# Teensy-Long.net
KiCad netlist of a schematic drawn in EAGLE
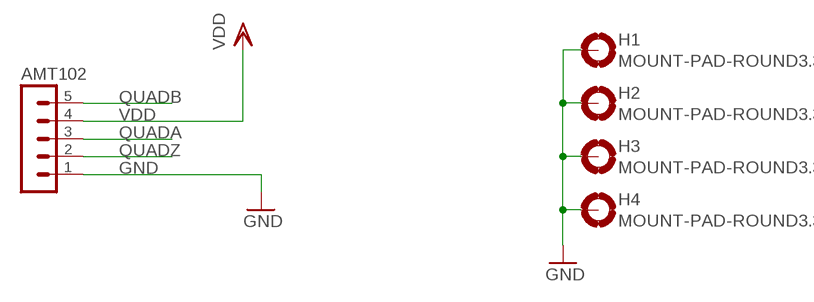
[diagram p0: schematic, sheet 1]
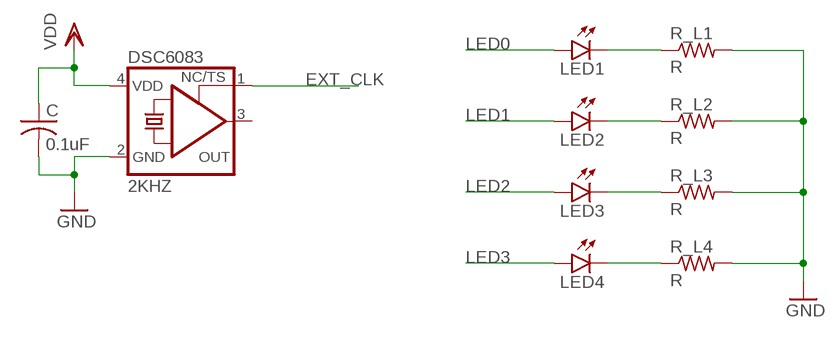
[diagram p1: schematic, sheet 2]
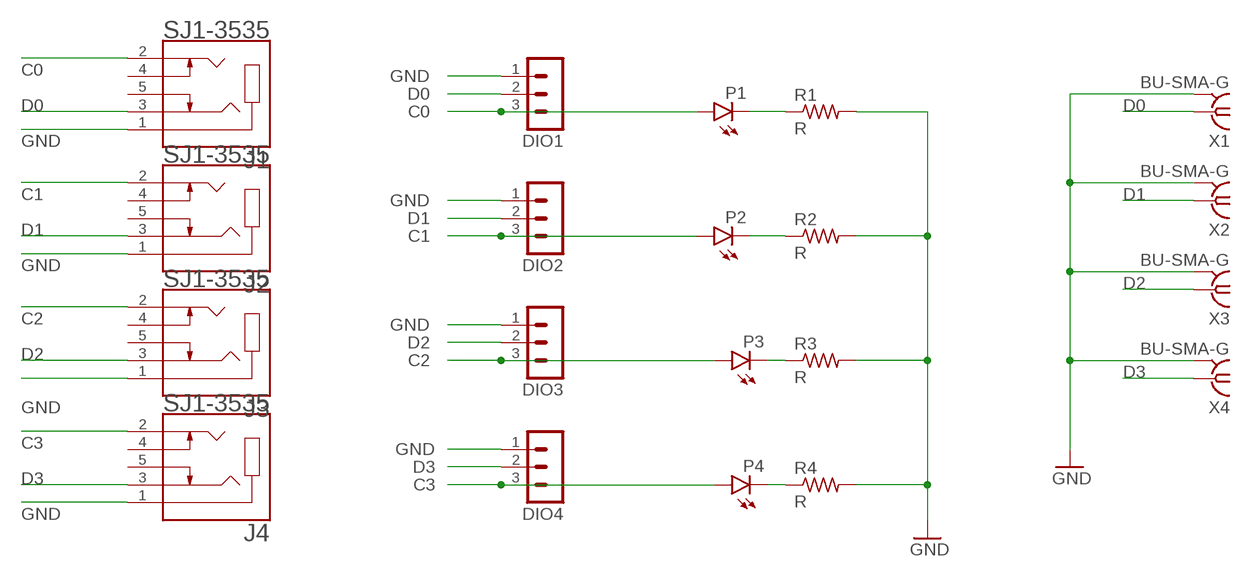
[diagram p2: schematic, sheet 3]
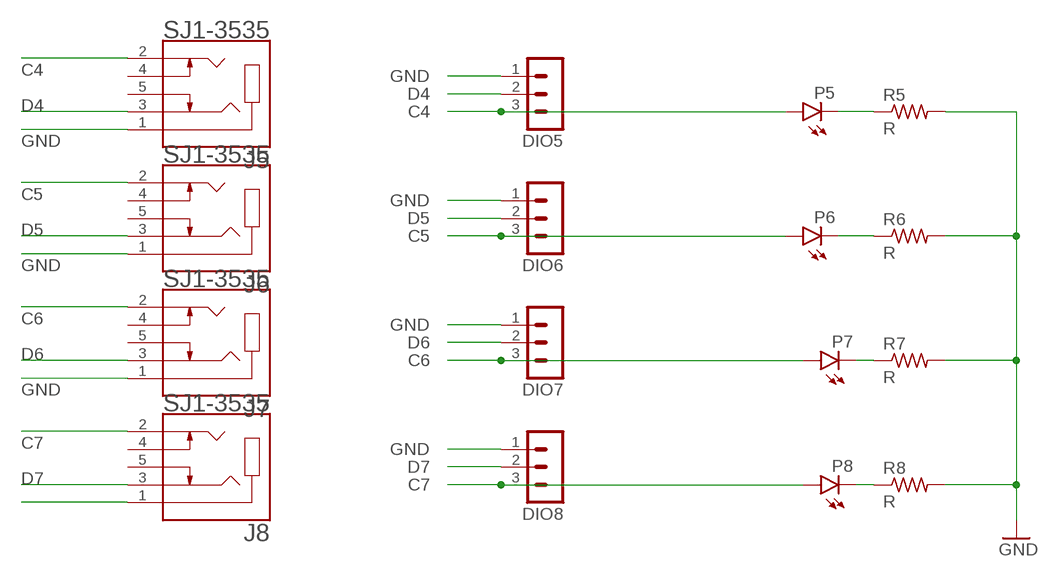
[diagram p3: schematic, sheet 4]
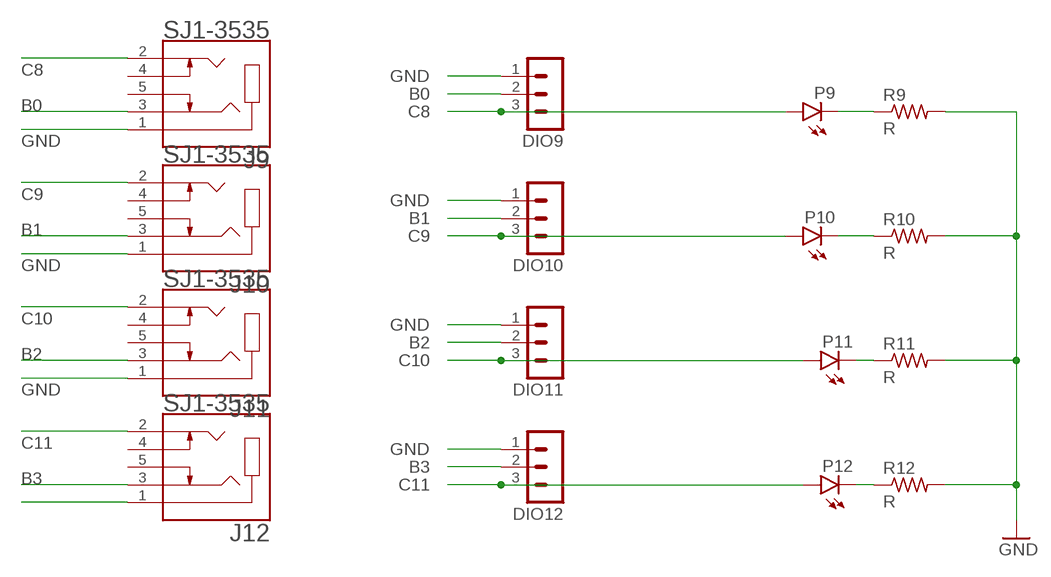
[diagram p4: schematic, sheet 5]
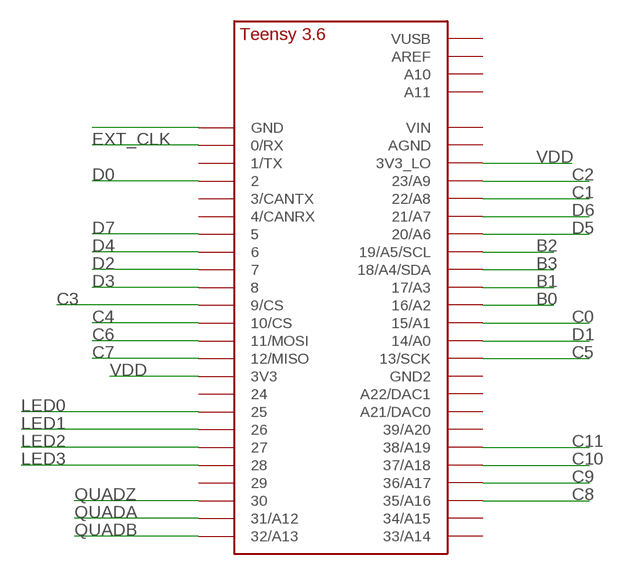
[diagram p5: schematic, sheet 6]

(export (version "E")
  (design (tool "Eeschema 10.0.6"))
  (components
    (comp (ref "C")
      (value "0.1uF")
      (footprint "eagle-import:C0603")
      (libsource (lib "eagle-import") (part "C-USC0603"))
    )
    (comp (ref "DSC6083")
      (value "2KHZ")
      (footprint "eagle-import:3.2X2.5_KXO-V96")
      (libsource (lib "eagle-import") (part "KXO-PXO/XO-V96"))
    )
    (comp (ref "LED1")
      (value "LEDCHIP-LED0603")
      (footprint "eagle-import:CHIP-LED0603")
      (libsource (lib "eagle-import") (part "LEDCHIP-LED0603"))
    )
    (comp (ref "LED2")
      (value "LEDCHIP-LED0603")
      (footprint "eagle-import:CHIP-LED0603")
      (libsource (lib "eagle-import") (part "LEDCHIP-LED0603"))
    )
    (comp (ref "LED3")
      (value "LEDCHIP-LED0603")
      (footprint "eagle-import:CHIP-LED0603")
      (libsource (lib "eagle-import") (part "LEDCHIP-LED0603"))
    )
    (comp (ref "LED4")
      (value "LEDCHIP-LED0603")
      (footprint "eagle-import:CHIP-LED0603")
      (libsource (lib "eagle-import") (part "LEDCHIP-LED0603"))
    )
    (comp (ref "R_L1")
      (value "R")
      (footprint "eagle-import:R0603")
      (libsource (lib "eagle-import") (part "R-US_R0603"))
    )
    (comp (ref "R_L2")
      (value "R")
      (footprint "eagle-import:R0603")
      (libsource (lib "eagle-import") (part "R-US_R0603"))
    )
    (comp (ref "R_L3")
      (value "R")
      (footprint "eagle-import:R0603")
      (libsource (lib "eagle-import") (part "R-US_R0603"))
    )
    (comp (ref "R_L4")
      (value "R")
      (footprint "eagle-import:R0603")
      (libsource (lib "eagle-import") (part "R-US_R0603"))
    )
    (comp (ref "U$3")
      (value "TEENSY_3.5/3.6_BASIC")
      (footprint "eagle-import:TEENSY_3.5_3.6_BASIC")
      (libsource (lib "eagle-import") (part "TEENSY_3.5/3.6_BASIC"))
    )
    (comp (ref "DIO9")
      (value "MA03-1")
      (footprint "eagle-import:MA03-1")
      (libsource (lib "eagle-import") (part "MA03-1"))
    )
    (comp (ref "DIO10")
      (value "MA03-1")
      (footprint "eagle-import:MA03-1")
      (libsource (lib "eagle-import") (part "MA03-1"))
    )
    (comp (ref "DIO11")
      (value "MA03-1")
      (footprint "eagle-import:MA03-1")
      (libsource (lib "eagle-import") (part "MA03-1"))
    )
    (comp (ref "DIO12")
      (value "MA03-1")
      (footprint "eagle-import:MA03-1")
      (libsource (lib "eagle-import") (part "MA03-1"))
    )
    (comp (ref "J9")
      (value "SJ1-3535")
      (footprint "eagle-import:CUI_SJ1-3535")
      (fields (field (name "MF") "CUI Devices"))
      (libsource (lib "eagle-import") (part "SJ1-3535"))
    )
    (comp (ref "J10")
      (value "SJ1-3535")
      (footprint "eagle-import:CUI_SJ1-3535")
      (fields (field (name "MF") "CUI Devices"))
      (libsource (lib "eagle-import") (part "SJ1-3535"))
    )
    (comp (ref "J11")
      (value "SJ1-3535")
      (footprint "eagle-import:CUI_SJ1-3535")
      (fields (field (name "MF") "CUI Devices"))
      (libsource (lib "eagle-import") (part "SJ1-3535"))
    )
    (comp (ref "J12")
      (value "SJ1-3535")
      (footprint "eagle-import:CUI_SJ1-3535")
      (fields (field (name "MF") "CUI Devices"))
      (libsource (lib "eagle-import") (part "SJ1-3535"))
    )
    (comp (ref "P9")
      (value "LEDCHIP-LED0603")
      (footprint "eagle-import:CHIP-LED0603")
      (libsource (lib "eagle-import") (part "LEDCHIP-LED0603"))
    )
    (comp (ref "P10")
      (value "LEDCHIP-LED0603")
      (footprint "eagle-import:CHIP-LED0603")
      (libsource (lib "eagle-import") (part "LEDCHIP-LED0603"))
    )
    (comp (ref "P11")
      (value "LEDCHIP-LED0603")
      (footprint "eagle-import:CHIP-LED0603")
      (libsource (lib "eagle-import") (part "LEDCHIP-LED0603"))
    )
    (comp (ref "P12")
      (value "LEDCHIP-LED0603")
      (footprint "eagle-import:CHIP-LED0603")
      (libsource (lib "eagle-import") (part "LEDCHIP-LED0603"))
    )
    (comp (ref "R9")
      (value "R")
      (footprint "eagle-import:R0603")
      (libsource (lib "eagle-import") (part "R-US_R0603"))
    )
    (comp (ref "R10")
      (value "R")
      (footprint "eagle-import:R0603")
      (libsource (lib "eagle-import") (part "R-US_R0603"))
    )
    (comp (ref "R11")
      (value "R")
      (footprint "eagle-import:R0603")
      (libsource (lib "eagle-import") (part "R-US_R0603"))
    )
    (comp (ref "R12")
      (value "R")
      (footprint "eagle-import:R0603")
      (libsource (lib "eagle-import") (part "R-US_R0603"))
    )
    (comp (ref "DIO5")
      (value "MA03-1")
      (footprint "eagle-import:MA03-1")
      (libsource (lib "eagle-import") (part "MA03-1"))
    )
    (comp (ref "DIO6")
      (value "MA03-1")
      (footprint "eagle-import:MA03-1")
      (libsource (lib "eagle-import") (part "MA03-1"))
    )
    (comp (ref "DIO7")
      (value "MA03-1")
      (footprint "eagle-import:MA03-1")
      (libsource (lib "eagle-import") (part "MA03-1"))
    )
    (comp (ref "DIO8")
      (value "MA03-1")
      (footprint "eagle-import:MA03-1")
      (libsource (lib "eagle-import") (part "MA03-1"))
    )
    (comp (ref "J5")
      (value "SJ1-3535")
      (footprint "eagle-import:CUI_SJ1-3535")
      (fields (field (name "MF") "CUI Devices"))
      (libsource (lib "eagle-import") (part "SJ1-3535"))
    )
    (comp (ref "J6")
      (value "SJ1-3535")
      (footprint "eagle-import:CUI_SJ1-3535")
      (fields (field (name "MF") "CUI Devices"))
      (libsource (lib "eagle-import") (part "SJ1-3535"))
    )
    (comp (ref "J7")
      (value "SJ1-3535")
      (footprint "eagle-import:CUI_SJ1-3535")
      (fields (field (name "MF") "CUI Devices"))
      (libsource (lib "eagle-import") (part "SJ1-3535"))
    )
    (comp (ref "J8")
      (value "SJ1-3535")
      (footprint "eagle-import:CUI_SJ1-3535")
      (fields (field (name "MF") "CUI Devices"))
      (libsource (lib "eagle-import") (part "SJ1-3535"))
    )
    (comp (ref "P5")
      (value "LEDCHIP-LED0603")
      (footprint "eagle-import:CHIP-LED0603")
      (libsource (lib "eagle-import") (part "LEDCHIP-LED0603"))
    )
    (comp (ref "P6")
      (value "LEDCHIP-LED0603")
      (footprint "eagle-import:CHIP-LED0603")
      (libsource (lib "eagle-import") (part "LEDCHIP-LED0603"))
    )
    (comp (ref "P7")
      (value "LEDCHIP-LED0603")
      (footprint "eagle-import:CHIP-LED0603")
      (libsource (lib "eagle-import") (part "LEDCHIP-LED0603"))
    )
    (comp (ref "P8")
      (value "LEDCHIP-LED0603")
      (footprint "eagle-import:CHIP-LED0603")
      (libsource (lib "eagle-import") (part "LEDCHIP-LED0603"))
    )
    (comp (ref "R5")
      (value "R")
      (footprint "eagle-import:R0603")
      (libsource (lib "eagle-import") (part "R-US_R0603"))
    )
    (comp (ref "R6")
      (value "R")
      (footprint "eagle-import:R0603")
      (libsource (lib "eagle-import") (part "R-US_R0603"))
    )
    (comp (ref "R7")
      (value "R")
      (footprint "eagle-import:R0603")
      (libsource (lib "eagle-import") (part "R-US_R0603"))
    )
    (comp (ref "R8")
      (value "R")
      (footprint "eagle-import:R0603")
      (libsource (lib "eagle-import") (part "R-US_R0603"))
    )
    (comp (ref "AMT102")
      (value "MA05-1")
      (footprint "eagle-import:MA05-1")
      (libsource (lib "eagle-import") (part "MA05-1"))
    )
    (comp (ref "H1")
      (value "MOUNT-PAD-ROUND3.3")
      (footprint "eagle-import:3,3-PAD")
      (libsource (lib "eagle-import") (part "MOUNT-PAD-ROUND3.3"))
    )
    (comp (ref "H2")
      (value "MOUNT-PAD-ROUND3.3")
      (footprint "eagle-import:3,3-PAD")
      (libsource (lib "eagle-import") (part "MOUNT-PAD-ROUND3.3"))
    )
    (comp (ref "H3")
      (value "MOUNT-PAD-ROUND3.3")
      (footprint "eagle-import:3,3-PAD")
      (libsource (lib "eagle-import") (part "MOUNT-PAD-ROUND3.3"))
    )
    (comp (ref "H4")
      (value "MOUNT-PAD-ROUND3.3")
      (footprint "eagle-import:3,3-PAD")
      (libsource (lib "eagle-import") (part "MOUNT-PAD-ROUND3.3"))
    )
    (comp (ref "DIO1")
      (value "MA03-1")
      (footprint "eagle-import:MA03-1")
      (libsource (lib "eagle-import") (part "MA03-1"))
    )
    (comp (ref "DIO2")
      (value "MA03-1")
      (footprint "eagle-import:MA03-1")
      (libsource (lib "eagle-import") (part "MA03-1"))
    )
    (comp (ref "DIO3")
      (value "MA03-1")
      (footprint "eagle-import:MA03-1")
      (libsource (lib "eagle-import") (part "MA03-1"))
    )
    (comp (ref "DIO4")
      (value "MA03-1")
      (footprint "eagle-import:MA03-1")
      (libsource (lib "eagle-import") (part "MA03-1"))
    )
    (comp (ref "J1")
      (value "SJ1-3535")
      (footprint "eagle-import:CUI_SJ1-3535")
      (fields (field (name "MF") "CUI Devices"))
      (libsource (lib "eagle-import") (part "SJ1-3535"))
    )
    (comp (ref "J2")
      (value "SJ1-3535")
      (footprint "eagle-import:CUI_SJ1-3535")
      (fields (field (name "MF") "CUI Devices"))
      (libsource (lib "eagle-import") (part "SJ1-3535"))
    )
    (comp (ref "J3")
      (value "SJ1-3535")
      (footprint "eagle-import:CUI_SJ1-3535")
      (fields (field (name "MF") "CUI Devices"))
      (libsource (lib "eagle-import") (part "SJ1-3535"))
    )
    (comp (ref "J4")
      (value "SJ1-3535")
      (footprint "eagle-import:CUI_SJ1-3535")
      (fields (field (name "MF") "CUI Devices"))
      (libsource (lib "eagle-import") (part "SJ1-3535"))
    )
    (comp (ref "P1")
      (value "LEDCHIP-LED0603")
      (footprint "eagle-import:CHIP-LED0603")
      (libsource (lib "eagle-import") (part "LEDCHIP-LED0603"))
    )
    (comp (ref "P2")
      (value "LEDCHIP-LED0603")
      (footprint "eagle-import:CHIP-LED0603")
      (libsource (lib "eagle-import") (part "LEDCHIP-LED0603"))
    )
    (comp (ref "P3")
      (value "LEDCHIP-LED0603")
      (footprint "eagle-import:CHIP-LED0603")
      (libsource (lib "eagle-import") (part "LEDCHIP-LED0603"))
    )
    (comp (ref "P4")
      (value "LEDCHIP-LED0603")
      (footprint "eagle-import:CHIP-LED0603")
      (libsource (lib "eagle-import") (part "LEDCHIP-LED0603"))
    )
    (comp (ref "R1")
      (value "R")
      (footprint "eagle-import:R0603")
      (libsource (lib "eagle-import") (part "R-US_R0603"))
    )
    (comp (ref "R2")
      (value "R")
      (footprint "eagle-import:R0603")
      (libsource (lib "eagle-import") (part "R-US_R0603"))
    )
    (comp (ref "R3")
      (value "R")
      (footprint "eagle-import:R0603")
      (libsource (lib "eagle-import") (part "R-US_R0603"))
    )
    (comp (ref "R4")
      (value "R")
      (footprint "eagle-import:R0603")
      (libsource (lib "eagle-import") (part "R-US_R0603"))
    )
    (comp (ref "X1")
      (value "BU-SMA-G")
      (footprint "eagle-import:BU-SMA-G")
      (libsource (lib "eagle-import") (part "BU-SMA-G"))
    )
    (comp (ref "X2")
      (value "BU-SMA-G")
      (footprint "eagle-import:BU-SMA-G")
      (libsource (lib "eagle-import") (part "BU-SMA-G"))
    )
    (comp (ref "X3")
      (value "BU-SMA-G")
      (footprint "eagle-import:BU-SMA-G")
      (libsource (lib "eagle-import") (part "BU-SMA-G"))
    )
    (comp (ref "X4")
      (value "BU-SMA-G")
      (footprint "eagle-import:BU-SMA-G")
      (libsource (lib "eagle-import") (part "BU-SMA-G"))
    )
  )
  (nets
    (net (code "1") (name "B0") (class "Default")
      (node (ref "DIO9") (pin "2") (pinfunction "2_2") (pintype "passive"))
      (node (ref "J9") (pin "3") (pinfunction "3_3") (pintype "passive"))
      (node (ref "U$3") (pin "16/A2") (pinfunction "16/A2_16/A2") (pintype "bidirectional"))
    )
    (net (code "2") (name "B1") (class "Default")
      (node (ref "DIO10") (pin "2") (pinfunction "2_2") (pintype "passive"))
      (node (ref "J10") (pin "3") (pinfunction "3_3") (pintype "passive"))
      (node (ref "U$3") (pin "17/A3") (pinfunction "17/A3_17/A3") (pintype "bidirectional"))
    )
    (net (code "3") (name "B2") (class "Default")
      (node (ref "DIO11") (pin "2") (pinfunction "2_2") (pintype "passive"))
      (node (ref "J11") (pin "3") (pinfunction "3_3") (pintype "passive"))
      (node (ref "U$3") (pin "19/A5/SCL") (pinfunction "19/A5/SCL_19/A5/SCL") (pintype "bidirectional"))
    )
    (net (code "4") (name "B3") (class "Default")
      (node (ref "DIO12") (pin "2") (pinfunction "2_2") (pintype "passive"))
      (node (ref "J12") (pin "3") (pinfunction "3_3") (pintype "passive"))
      (node (ref "U$3") (pin "18/A4/SDA") (pinfunction "18/A4/SDA_18/A4/SDA") (pintype "bidirectional"))
    )
    (net (code "5") (name "C0") (class "Default")
      (node (ref "DIO1") (pin "3") (pinfunction "3_3") (pintype "passive"))
      (node (ref "J1") (pin "2") (pinfunction "2_2") (pintype "passive"))
      (node (ref "P1") (pin "A") (pinfunction "A_A") (pintype "passive"))
      (node (ref "U$3") (pin "15/A1") (pinfunction "15/A1_15/A1") (pintype "bidirectional"))
    )
    (net (code "6") (name "C1") (class "Default")
      (node (ref "DIO2") (pin "3") (pinfunction "3_3") (pintype "passive"))
      (node (ref "J2") (pin "2") (pinfunction "2_2") (pintype "passive"))
      (node (ref "P2") (pin "A") (pinfunction "A_A") (pintype "passive"))
      (node (ref "U$3") (pin "22/A8") (pinfunction "22/A8_22/A8") (pintype "bidirectional"))
    )
    (net (code "7") (name "C2") (class "Default")
      (node (ref "DIO3") (pin "3") (pinfunction "3_3") (pintype "passive"))
      (node (ref "J3") (pin "2") (pinfunction "2_2") (pintype "passive"))
      (node (ref "P3") (pin "A") (pinfunction "A_A") (pintype "passive"))
      (node (ref "U$3") (pin "23/A9") (pinfunction "23/A9_23/A9") (pintype "bidirectional"))
    )
    (net (code "8") (name "C3") (class "Default")
      (node (ref "DIO4") (pin "3") (pinfunction "3_3") (pintype "passive"))
      (node (ref "J4") (pin "2") (pinfunction "2_2") (pintype "passive"))
      (node (ref "P4") (pin "A") (pinfunction "A_A") (pintype "passive"))
      (node (ref "U$3") (pin "9/CS") (pinfunction "9/CS_9/CS") (pintype "bidirectional"))
    )
    (net (code "9") (name "C4") (class "Default")
      (node (ref "DIO5") (pin "3") (pinfunction "3_3") (pintype "passive"))
      (node (ref "J5") (pin "2") (pinfunction "2_2") (pintype "passive"))
      (node (ref "P5") (pin "A") (pinfunction "A_A") (pintype "passive"))
      (node (ref "U$3") (pin "10/CS") (pinfunction "10/CS_10/CS") (pintype "bidirectional"))
    )
    (net (code "10") (name "C5") (class "Default")
      (node (ref "DIO6") (pin "3") (pinfunction "3_3") (pintype "passive"))
      (node (ref "J6") (pin "2") (pinfunction "2_2") (pintype "passive"))
      (node (ref "P6") (pin "A") (pinfunction "A_A") (pintype "passive"))
      (node (ref "U$3") (pin "13/SCK") (pinfunction "13/SCK_13/SCK") (pintype "bidirectional"))
    )
    (net (code "11") (name "C6") (class "Default")
      (node (ref "DIO7") (pin "3") (pinfunction "3_3") (pintype "passive"))
      (node (ref "J7") (pin "2") (pinfunction "2_2") (pintype "passive"))
      (node (ref "P7") (pin "A") (pinfunction "A_A") (pintype "passive"))
      (node (ref "U$3") (pin "11/MOSI") (pinfunction "11/MOSI_11/MOSI") (pintype "bidirectional"))
    )
    (net (code "12") (name "C7") (class "Default")
      (node (ref "DIO8") (pin "3") (pinfunction "3_3") (pintype "passive"))
      (node (ref "J8") (pin "2") (pinfunction "2_2") (pintype "passive"))
      (node (ref "P8") (pin "A") (pinfunction "A_A") (pintype "passive"))
      (node (ref "U$3") (pin "12/MISO") (pinfunction "12/MISO_12/MISO") (pintype "bidirectional"))
    )
    (net (code "13") (name "C8") (class "Default")
      (node (ref "DIO9") (pin "3") (pinfunction "3_3") (pintype "passive"))
      (node (ref "J9") (pin "2") (pinfunction "2_2") (pintype "passive"))
      (node (ref "P9") (pin "A") (pinfunction "A_A") (pintype "passive"))
      (node (ref "U$3") (pin "35/A16") (pinfunction "35/A16_35/A16") (pintype "bidirectional"))
    )
    (net (code "14") (name "C9") (class "Default")
      (node (ref "DIO10") (pin "3") (pinfunction "3_3") (pintype "passive"))
      (node (ref "J10") (pin "2") (pinfunction "2_2") (pintype "passive"))
      (node (ref "P10") (pin "A") (pinfunction "A_A") (pintype "passive"))
      (node (ref "U$3") (pin "36/A17") (pinfunction "36/A17_36/A17") (pintype "bidirectional"))
    )
    (net (code "15") (name "C10") (class "Default")
      (node (ref "DIO11") (pin "3") (pinfunction "3_3") (pintype "passive"))
      (node (ref "J11") (pin "2") (pinfunction "2_2") (pintype "passive"))
      (node (ref "P11") (pin "A") (pinfunction "A_A") (pintype "passive"))
      (node (ref "U$3") (pin "37/A18") (pinfunction "37/A18_37/A18") (pintype "bidirectional"))
    )
    (net (code "16") (name "C11") (class "Default")
      (node (ref "DIO12") (pin "3") (pinfunction "3_3") (pintype "passive"))
      (node (ref "J12") (pin "2") (pinfunction "2_2") (pintype "passive"))
      (node (ref "P12") (pin "A") (pinfunction "A_A") (pintype "passive"))
      (node (ref "U$3") (pin "38/A19") (pinfunction "38/A19_38/A19") (pintype "bidirectional"))
    )
    (net (code "17") (name "D0") (class "Default")
      (node (ref "DIO1") (pin "2") (pinfunction "2_2") (pintype "passive"))
      (node (ref "J1") (pin "3") (pinfunction "3_3") (pintype "passive"))
      (node (ref "U$3") (pin "2") (pinfunction "2_2") (pintype "bidirectional"))
      (node (ref "X1") (pin "1") (pinfunction "1_1") (pintype "passive"))
    )
    (net (code "18") (name "D1") (class "Default")
      (node (ref "DIO2") (pin "2") (pinfunction "2_2") (pintype "passive"))
      (node (ref "J2") (pin "3") (pinfunction "3_3") (pintype "passive"))
      (node (ref "U$3") (pin "14/A0") (pinfunction "14/A0_14/A0") (pintype "bidirectional"))
      (node (ref "X2") (pin "1") (pinfunction "1_1") (pintype "passive"))
    )
    (net (code "19") (name "D2") (class "Default")
      (node (ref "DIO3") (pin "2") (pinfunction "2_2") (pintype "passive"))
      (node (ref "J3") (pin "3") (pinfunction "3_3") (pintype "passive"))
      (node (ref "U$3") (pin "7") (pinfunction "7_7") (pintype "bidirectional"))
      (node (ref "X3") (pin "1") (pinfunction "1_1") (pintype "passive"))
    )
    (net (code "20") (name "D3") (class "Default")
      (node (ref "DIO4") (pin "2") (pinfunction "2_2") (pintype "passive"))
      (node (ref "J4") (pin "3") (pinfunction "3_3") (pintype "passive"))
      (node (ref "U$3") (pin "8") (pinfunction "8_8") (pintype "bidirectional"))
      (node (ref "X4") (pin "1") (pinfunction "1_1") (pintype "passive"))
    )
    (net (code "21") (name "D4") (class "Default")
      (node (ref "DIO5") (pin "2") (pinfunction "2_2") (pintype "passive"))
      (node (ref "J5") (pin "3") (pinfunction "3_3") (pintype "passive"))
      (node (ref "U$3") (pin "6") (pinfunction "6_6") (pintype "bidirectional"))
    )
    (net (code "22") (name "D5") (class "Default")
      (node (ref "DIO6") (pin "2") (pinfunction "2_2") (pintype "passive"))
      (node (ref "J6") (pin "3") (pinfunction "3_3") (pintype "passive"))
      (node (ref "U$3") (pin "20/A6") (pinfunction "20/A6_20/A6") (pintype "bidirectional"))
    )
    (net (code "23") (name "D6") (class "Default")
      (node (ref "DIO7") (pin "2") (pinfunction "2_2") (pintype "passive"))
      (node (ref "J7") (pin "3") (pinfunction "3_3") (pintype "passive"))
      (node (ref "U$3") (pin "21/A7") (pinfunction "21/A7_21/A7") (pintype "bidirectional"))
    )
    (net (code "24") (name "D7") (class "Default")
      (node (ref "DIO8") (pin "2") (pinfunction "2_2") (pintype "passive"))
      (node (ref "J8") (pin "3") (pinfunction "3_3") (pintype "passive"))
      (node (ref "U$3") (pin "5") (pinfunction "5_5") (pintype "bidirectional"))
    )
    (net (code "25") (name "EXT_CLK") (class "Default")
      (node (ref "DSC6083") (pin "1") (pinfunction "TS_1") (pintype "passive"))
      (node (ref "U$3") (pin "0/RX") (pinfunction "0/RX_0/RX") (pintype "bidirectional"))
    )
    (net (code "26") (name "GND") (class "Default")
      (node (ref "AMT102") (pin "1") (pinfunction "1_1") (pintype "passive"))
      (node (ref "C") (pin "2") (pinfunction "2_2") (pintype "passive"))
      (node (ref "DIO1") (pin "1") (pinfunction "1_1") (pintype "passive"))
      (node (ref "DIO10") (pin "1") (pinfunction "1_1") (pintype "passive"))
      (node (ref "DIO11") (pin "1") (pinfunction "1_1") (pintype "passive"))
      (node (ref "DIO12") (pin "1") (pinfunction "1_1") (pintype "passive"))
      (node (ref "DIO2") (pin "1") (pinfunction "1_1") (pintype "passive"))
      (node (ref "DIO3") (pin "1") (pinfunction "1_1") (pintype "passive"))
      (node (ref "DIO4") (pin "1") (pinfunction "1_1") (pintype "passive"))
      (node (ref "DIO5") (pin "1") (pinfunction "1_1") (pintype "passive"))
      (node (ref "DIO6") (pin "1") (pinfunction "1_1") (pintype "passive"))
      (node (ref "DIO7") (pin "1") (pinfunction "1_1") (pintype "passive"))
      (node (ref "DIO8") (pin "1") (pinfunction "1_1") (pintype "passive"))
      (node (ref "DIO9") (pin "1") (pinfunction "1_1") (pintype "passive"))
      (node (ref "DSC6083") (pin "2") (pinfunction "GND_2") (pintype "power_in"))
      (node (ref "H1") (pin "B3,3") (pinfunction "MOUNT_B3,3") (pintype "passive"))
      (node (ref "H2") (pin "B3,3") (pinfunction "MOUNT_B3,3") (pintype "passive"))
      (node (ref "H3") (pin "B3,3") (pinfunction "MOUNT_B3,3") (pintype "passive"))
      (node (ref "H4") (pin "B3,3") (pinfunction "MOUNT_B3,3") (pintype "passive"))
      (node (ref "J1") (pin "1") (pinfunction "1_1") (pintype "passive"))
      (node (ref "J10") (pin "1") (pinfunction "1_1") (pintype "passive"))
      (node (ref "J11") (pin "1") (pinfunction "1_1") (pintype "passive"))
      (node (ref "J12") (pin "1") (pinfunction "1_1") (pintype "passive"))
      (node (ref "J2") (pin "1") (pinfunction "1_1") (pintype "passive"))
      (node (ref "J3") (pin "1") (pinfunction "1_1") (pintype "passive"))
      (node (ref "J4") (pin "1") (pinfunction "1_1") (pintype "passive"))
      (node (ref "J5") (pin "1") (pinfunction "1_1") (pintype "passive"))
      (node (ref "J6") (pin "1") (pinfunction "1_1") (pintype "passive"))
      (node (ref "J7") (pin "1") (pinfunction "1_1") (pintype "passive"))
      (node (ref "J8") (pin "1") (pinfunction "1_1") (pintype "passive"))
      (node (ref "J9") (pin "1") (pinfunction "1_1") (pintype "passive"))
      (node (ref "R1") (pin "2") (pinfunction "2_2") (pintype "passive"))
      (node (ref "R10") (pin "2") (pinfunction "2_2") (pintype "passive"))
      (node (ref "R11") (pin "2") (pinfunction "2_2") (pintype "passive"))
      (node (ref "R12") (pin "2") (pinfunction "2_2") (pintype "passive"))
      (node (ref "R2") (pin "2") (pinfunction "2_2") (pintype "passive"))
      (node (ref "R3") (pin "2") (pinfunction "2_2") (pintype "passive"))
      (node (ref "R4") (pin "2") (pinfunction "2_2") (pintype "passive"))
      (node (ref "R5") (pin "2") (pinfunction "2_2") (pintype "passive"))
      (node (ref "R6") (pin "2") (pinfunction "2_2") (pintype "passive"))
      (node (ref "R7") (pin "2") (pinfunction "2_2") (pintype "passive"))
      (node (ref "R8") (pin "2") (pinfunction "2_2") (pintype "passive"))
      (node (ref "R9") (pin "2") (pinfunction "2_2") (pintype "passive"))
      (node (ref "R_L1") (pin "2") (pinfunction "2_2") (pintype "passive"))
      (node (ref "R_L2") (pin "2") (pinfunction "2_2") (pintype "passive"))
      (node (ref "R_L3") (pin "2") (pinfunction "2_2") (pintype "passive"))
      (node (ref "R_L4") (pin "2") (pinfunction "2_2") (pintype "passive"))
      (node (ref "U$3") (pin "GND") (pinfunction "GND_GND") (pintype "bidirectional"))
      (node (ref "X1") (pin "2") (pinfunction "2_2") (pintype "passive"))
      (node (ref "X1") (pin "3") (pinfunction "2_3") (pintype "passive"))
      (node (ref "X1") (pin "4") (pinfunction "2_4") (pintype "passive"))
      (node (ref "X1") (pin "5") (pinfunction "2_5") (pintype "passive"))
      (node (ref "X2") (pin "2") (pinfunction "2_2") (pintype "passive"))
      (node (ref "X2") (pin "3") (pinfunction "2_3") (pintype "passive"))
      (node (ref "X2") (pin "4") (pinfunction "2_4") (pintype "passive"))
      (node (ref "X2") (pin "5") (pinfunction "2_5") (pintype "passive"))
      (node (ref "X3") (pin "2") (pinfunction "2_2") (pintype "passive"))
      (node (ref "X3") (pin "3") (pinfunction "2_3") (pintype "passive"))
      (node (ref "X3") (pin "4") (pinfunction "2_4") (pintype "passive"))
      (node (ref "X3") (pin "5") (pinfunction "2_5") (pintype "passive"))
      (node (ref "X4") (pin "2") (pinfunction "2_2") (pintype "passive"))
      (node (ref "X4") (pin "3") (pinfunction "2_3") (pintype "passive"))
      (node (ref "X4") (pin "4") (pinfunction "2_4") (pintype "passive"))
      (node (ref "X4") (pin "5") (pinfunction "2_5") (pintype "passive"))
    )
    (net (code "27") (name "LED0") (class "Default")
      (node (ref "LED1") (pin "A") (pinfunction "A_A") (pintype "passive"))
      (node (ref "U$3") (pin "25") (pinfunction "25_25") (pintype "bidirectional"))
    )
    (net (code "28") (name "LED1") (class "Default")
      (node (ref "LED2") (pin "A") (pinfunction "A_A") (pintype "passive"))
      (node (ref "U$3") (pin "26") (pinfunction "26_26") (pintype "bidirectional"))
    )
    (net (code "29") (name "LED2") (class "Default")
      (node (ref "LED3") (pin "A") (pinfunction "A_A") (pintype "passive"))
      (node (ref "U$3") (pin "27") (pinfunction "27_27") (pintype "bidirectional"))
    )
    (net (code "30") (name "LED3") (class "Default")
      (node (ref "LED4") (pin "A") (pinfunction "A_A") (pintype "passive"))
      (node (ref "U$3") (pin "28") (pinfunction "28_28") (pintype "bidirectional"))
    )
    (net (code "31") (name "Net-(LED1-PadC)") (class "Default")
      (node (ref "LED1") (pin "C") (pinfunction "C_C") (pintype "passive"))
      (node (ref "R_L1") (pin "1") (pinfunction "1_1") (pintype "passive"))
    )
    (net (code "32") (name "Net-(LED2-PadC)") (class "Default")
      (node (ref "LED2") (pin "C") (pinfunction "C_C") (pintype "passive"))
      (node (ref "R_L2") (pin "1") (pinfunction "1_1") (pintype "passive"))
    )
    (net (code "33") (name "Net-(LED3-PadC)") (class "Default")
      (node (ref "LED3") (pin "C") (pinfunction "C_C") (pintype "passive"))
      (node (ref "R_L3") (pin "1") (pinfunction "1_1") (pintype "passive"))
    )
    (net (code "34") (name "Net-(LED4-PadC)") (class "Default")
      (node (ref "LED4") (pin "C") (pinfunction "C_C") (pintype "passive"))
      (node (ref "R_L4") (pin "1") (pinfunction "1_1") (pintype "passive"))
    )
    (net (code "35") (name "Net-(P1-PadC)") (class "Default")
      (node (ref "P1") (pin "C") (pinfunction "C_C") (pintype "passive"))
      (node (ref "R1") (pin "1") (pinfunction "1_1") (pintype "passive"))
    )
    (net (code "36") (name "Net-(P2-PadC)") (class "Default")
      (node (ref "P2") (pin "C") (pinfunction "C_C") (pintype "passive"))
      (node (ref "R2") (pin "1") (pinfunction "1_1") (pintype "passive"))
    )
    (net (code "37") (name "Net-(P3-PadC)") (class "Default")
      (node (ref "P3") (pin "C") (pinfunction "C_C") (pintype "passive"))
      (node (ref "R3") (pin "1") (pinfunction "1_1") (pintype "passive"))
    )
    (net (code "38") (name "Net-(P4-PadC)") (class "Default")
      (node (ref "P4") (pin "C") (pinfunction "C_C") (pintype "passive"))
      (node (ref "R4") (pin "1") (pinfunction "1_1") (pintype "passive"))
    )
    (net (code "39") (name "Net-(P5-PadC)") (class "Default")
      (node (ref "P5") (pin "C") (pinfunction "C_C") (pintype "passive"))
      (node (ref "R5") (pin "1") (pinfunction "1_1") (pintype "passive"))
    )
    (net (code "40") (name "Net-(P6-PadC)") (class "Default")
      (node (ref "P6") (pin "C") (pinfunction "C_C") (pintype "passive"))
      (node (ref "R6") (pin "1") (pinfunction "1_1") (pintype "passive"))
    )
    (net (code "41") (name "Net-(P7-PadC)") (class "Default")
      (node (ref "P7") (pin "C") (pinfunction "C_C") (pintype "passive"))
      (node (ref "R7") (pin "1") (pinfunction "1_1") (pintype "passive"))
    )
    (net (code "42") (name "Net-(P8-PadC)") (class "Default")
      (node (ref "P8") (pin "C") (pinfunction "C_C") (pintype "passive"))
      (node (ref "R8") (pin "1") (pinfunction "1_1") (pintype "passive"))
    )
    (net (code "43") (name "Net-(P9-PadC)") (class "Default")
      (node (ref "P9") (pin "C") (pinfunction "C_C") (pintype "passive"))
      (node (ref "R9") (pin "1") (pinfunction "1_1") (pintype "passive"))
    )
    (net (code "44") (name "Net-(P10-PadC)") (class "Default")
      (node (ref "P10") (pin "C") (pinfunction "C_C") (pintype "passive"))
      (node (ref "R10") (pin "1") (pinfunction "1_1") (pintype "passive"))
    )
    (net (code "45") (name "Net-(P11-PadC)") (class "Default")
      (node (ref "P11") (pin "C") (pinfunction "C_C") (pintype "passive"))
      (node (ref "R11") (pin "1") (pinfunction "1_1") (pintype "passive"))
    )
    (net (code "46") (name "Net-(P12-PadC)") (class "Default")
      (node (ref "P12") (pin "C") (pinfunction "C_C") (pintype "passive"))
      (node (ref "R12") (pin "1") (pinfunction "1_1") (pintype "passive"))
    )
    (net (code "47") (name "QUADA") (class "Default")
      (node (ref "AMT102") (pin "3") (pinfunction "3_3") (pintype "passive"))
      (node (ref "U$3") (pin "31/A12") (pinfunction "31/A12_31/A12") (pintype "bidirectional"))
    )
    (net (code "48") (name "QUADB") (class "Default")
      (node (ref "AMT102") (pin "5") (pinfunction "5_5") (pintype "passive"))
      (node (ref "U$3") (pin "32/A13") (pinfunction "32/A13_32/A13") (pintype "bidirectional"))
    )
    (net (code "49") (name "QUADZ") (class "Default")
      (node (ref "AMT102") (pin "2") (pinfunction "2_2") (pintype "passive"))
      (node (ref "U$3") (pin "30") (pinfunction "30_30") (pintype "bidirectional"))
    )
    (net (code "50") (name "VDD") (class "Default")
      (node (ref "AMT102") (pin "4") (pinfunction "4_4") (pintype "passive"))
      (node (ref "C") (pin "1") (pinfunction "1_1") (pintype "passive"))
      (node (ref "DSC6083") (pin "4") (pinfunction "VDD_4") (pintype "power_in"))
      (node (ref "U$3") (pin "3V3") (pinfunction "3V3_3V3") (pintype "bidirectional"))
      (node (ref "U$3") (pin "3V3_LO") (pinfunction "3V3_LO_3V3_LO") (pintype "bidirectional"))
    )
    (net (code "51") (name "unconnected-(DSC6083-OUT-Pad3)") (class "Default")
      (node (ref "DSC6083") (pin "3") (pinfunction "OUT_3") (pintype "output"))
    )
    (net (code "52") (name "unconnected-(J1-Pad4)") (class "Default")
      (node (ref "J1") (pin "4") (pinfunction "4_4") (pintype "passive"))
    )
    (net (code "53") (name "unconnected-(J1-Pad5)") (class "Default")
      (node (ref "J1") (pin "5") (pinfunction "5_5") (pintype "passive"))
    )
    (net (code "54") (name "unconnected-(J2-Pad4)") (class "Default")
      (node (ref "J2") (pin "4") (pinfunction "4_4") (pintype "passive"))
    )
    (net (code "55") (name "unconnected-(J2-Pad5)") (class "Default")
      (node (ref "J2") (pin "5") (pinfunction "5_5") (pintype "passive"))
    )
    (net (code "56") (name "unconnected-(J3-Pad4)") (class "Default")
      (node (ref "J3") (pin "4") (pinfunction "4_4") (pintype "passive"))
    )
    (net (code "57") (name "unconnected-(J3-Pad5)") (class "Default")
      (node (ref "J3") (pin "5") (pinfunction "5_5") (pintype "passive"))
    )
    (net (code "58") (name "unconnected-(J4-Pad4)") (class "Default")
      (node (ref "J4") (pin "4") (pinfunction "4_4") (pintype "passive"))
    )
    (net (code "59") (name "unconnected-(J4-Pad5)") (class "Default")
      (node (ref "J4") (pin "5") (pinfunction "5_5") (pintype "passive"))
    )
    (net (code "60") (name "unconnected-(J5-Pad4)") (class "Default")
      (node (ref "J5") (pin "4") (pinfunction "4_4") (pintype "passive"))
    )
    (net (code "61") (name "unconnected-(J5-Pad5)") (class "Default")
      (node (ref "J5") (pin "5") (pinfunction "5_5") (pintype "passive"))
    )
    (net (code "62") (name "unconnected-(J6-Pad4)") (class "Default")
      (node (ref "J6") (pin "4") (pinfunction "4_4") (pintype "passive"))
    )
    (net (code "63") (name "unconnected-(J6-Pad5)") (class "Default")
      (node (ref "J6") (pin "5") (pinfunction "5_5") (pintype "passive"))
    )
    (net (code "64") (name "unconnected-(J7-Pad4)") (class "Default")
      (node (ref "J7") (pin "4") (pinfunction "4_4") (pintype "passive"))
    )
    (net (code "65") (name "unconnected-(J7-Pad5)") (class "Default")
      (node (ref "J7") (pin "5") (pinfunction "5_5") (pintype "passive"))
    )
    (net (code "66") (name "unconnected-(J8-Pad4)") (class "Default")
      (node (ref "J8") (pin "4") (pinfunction "4_4") (pintype "passive"))
    )
    (net (code "67") (name "unconnected-(J8-Pad5)") (class "Default")
      (node (ref "J8") (pin "5") (pinfunction "5_5") (pintype "passive"))
    )
    (net (code "68") (name "unconnected-(J9-Pad4)") (class "Default")
      (node (ref "J9") (pin "4") (pinfunction "4_4") (pintype "passive"))
    )
    (net (code "69") (name "unconnected-(J9-Pad5)") (class "Default")
      (node (ref "J9") (pin "5") (pinfunction "5_5") (pintype "passive"))
    )
    (net (code "70") (name "unconnected-(J10-Pad4)") (class "Default")
      (node (ref "J10") (pin "4") (pinfunction "4_4") (pintype "passive"))
    )
    (net (code "71") (name "unconnected-(J10-Pad5)") (class "Default")
      (node (ref "J10") (pin "5") (pinfunction "5_5") (pintype "passive"))
    )
    (net (code "72") (name "unconnected-(J11-Pad4)") (class "Default")
      (node (ref "J11") (pin "4") (pinfunction "4_4") (pintype "passive"))
    )
    (net (code "73") (name "unconnected-(J11-Pad5)") (class "Default")
      (node (ref "J11") (pin "5") (pinfunction "5_5") (pintype "passive"))
    )
    (net (code "74") (name "unconnected-(J12-Pad4)") (class "Default")
      (node (ref "J12") (pin "4") (pinfunction "4_4") (pintype "passive"))
    )
    (net (code "75") (name "unconnected-(J12-Pad5)") (class "Default")
      (node (ref "J12") (pin "5") (pinfunction "5_5") (pintype "passive"))
    )
    (net (code "76") (name "unconnected-(U$3-A21{slash}DAC0-Pad21{slash}DAC0)") (class "Default")
      (node (ref "U$3") (pin "21/DAC0") (pinfunction "A21/DAC0_21/DAC0") (pintype "bidirectional"))
    )
    (net (code "77") (name "unconnected-(U$3-Pad1{slash}TX)") (class "Default")
      (node (ref "U$3") (pin "1/TX") (pinfunction "1/TX_1/TX") (pintype "bidirectional"))
    )
    (net (code "78") (name "unconnected-(U$3-Pad3{slash}CANTX)") (class "Default")
      (node (ref "U$3") (pin "3/CANTX") (pinfunction "3/CANTX_3/CANTX") (pintype "bidirectional"))
    )
    (net (code "79") (name "unconnected-(U$3-Pad4{slash}CANRX)") (class "Default")
      (node (ref "U$3") (pin "4/CANRX") (pinfunction "4/CANRX_4/CANRX") (pintype "bidirectional"))
    )
    (net (code "80") (name "unconnected-(U$3-Pad24)") (class "Default")
      (node (ref "U$3") (pin "24") (pinfunction "24_24") (pintype "bidirectional"))
    )
    (net (code "81") (name "unconnected-(U$3-Pad29)") (class "Default")
      (node (ref "U$3") (pin "29") (pinfunction "29_29") (pintype "bidirectional"))
    )
    (net (code "82") (name "unconnected-(U$3-Pad33{slash}A14)") (class "Default")
      (node (ref "U$3") (pin "33/A14") (pinfunction "33/A14_33/A14") (pintype "bidirectional"))
    )
    (net (code "83") (name "unconnected-(U$3-Pad34{slash}A15)") (class "Default")
      (node (ref "U$3") (pin "34/A15") (pinfunction "34/A15_34/A15") (pintype "bidirectional"))
    )
    (net (code "84") (name "unconnected-(U$3-Pad39{slash}A20)") (class "Default")
      (node (ref "U$3") (pin "39/A20") (pinfunction "39/A20_39/A20") (pintype "bidirectional"))
    )
    (net (code "85") (name "unconnected-(U$3-PadA10)") (class "Default")
      (node (ref "U$3") (pin "A10") (pinfunction "A10_A10") (pintype "bidirectional"))
    )
    (net (code "86") (name "unconnected-(U$3-PadA11)") (class "Default")
      (node (ref "U$3") (pin "A11") (pinfunction "A11_A11") (pintype "bidirectional"))
    )
    (net (code "87") (name "unconnected-(U$3-PadA22{slash}DAC1)") (class "Default")
      (node (ref "U$3") (pin "A22/DAC1") (pinfunction "A22/DAC1_A22/DAC1") (pintype "bidirectional"))
    )
    (net (code "88") (name "unconnected-(U$3-PadAGND)") (class "Default")
      (node (ref "U$3") (pin "AGND") (pinfunction "AGND_AGND") (pintype "bidirectional"))
    )
    (net (code "89") (name "unconnected-(U$3-PadAREF)") (class "Default")
      (node (ref "U$3") (pin "AREF") (pinfunction "AREF_AREF") (pintype "bidirectional"))
    )
    (net (code "90") (name "unconnected-(U$3-PadGND2)") (class "Default")
      (node (ref "U$3") (pin "GND2") (pinfunction "GND2_GND2") (pintype "bidirectional"))
    )
    (net (code "91") (name "unconnected-(U$3-PadVIN)") (class "Default")
      (node (ref "U$3") (pin "VIN") (pinfunction "VIN_VIN") (pintype "bidirectional"))
    )
    (net (code "92") (name "unconnected-(U$3-PadVUSB)") (class "Default")
      (node (ref "U$3") (pin "VUSB") (pinfunction "VUSB_VUSB") (pintype "bidirectional"))
    )
  )
)
